# WeMos-WLED-V01-008.net
KiCad netlist of a schematic drawn in EAGLE
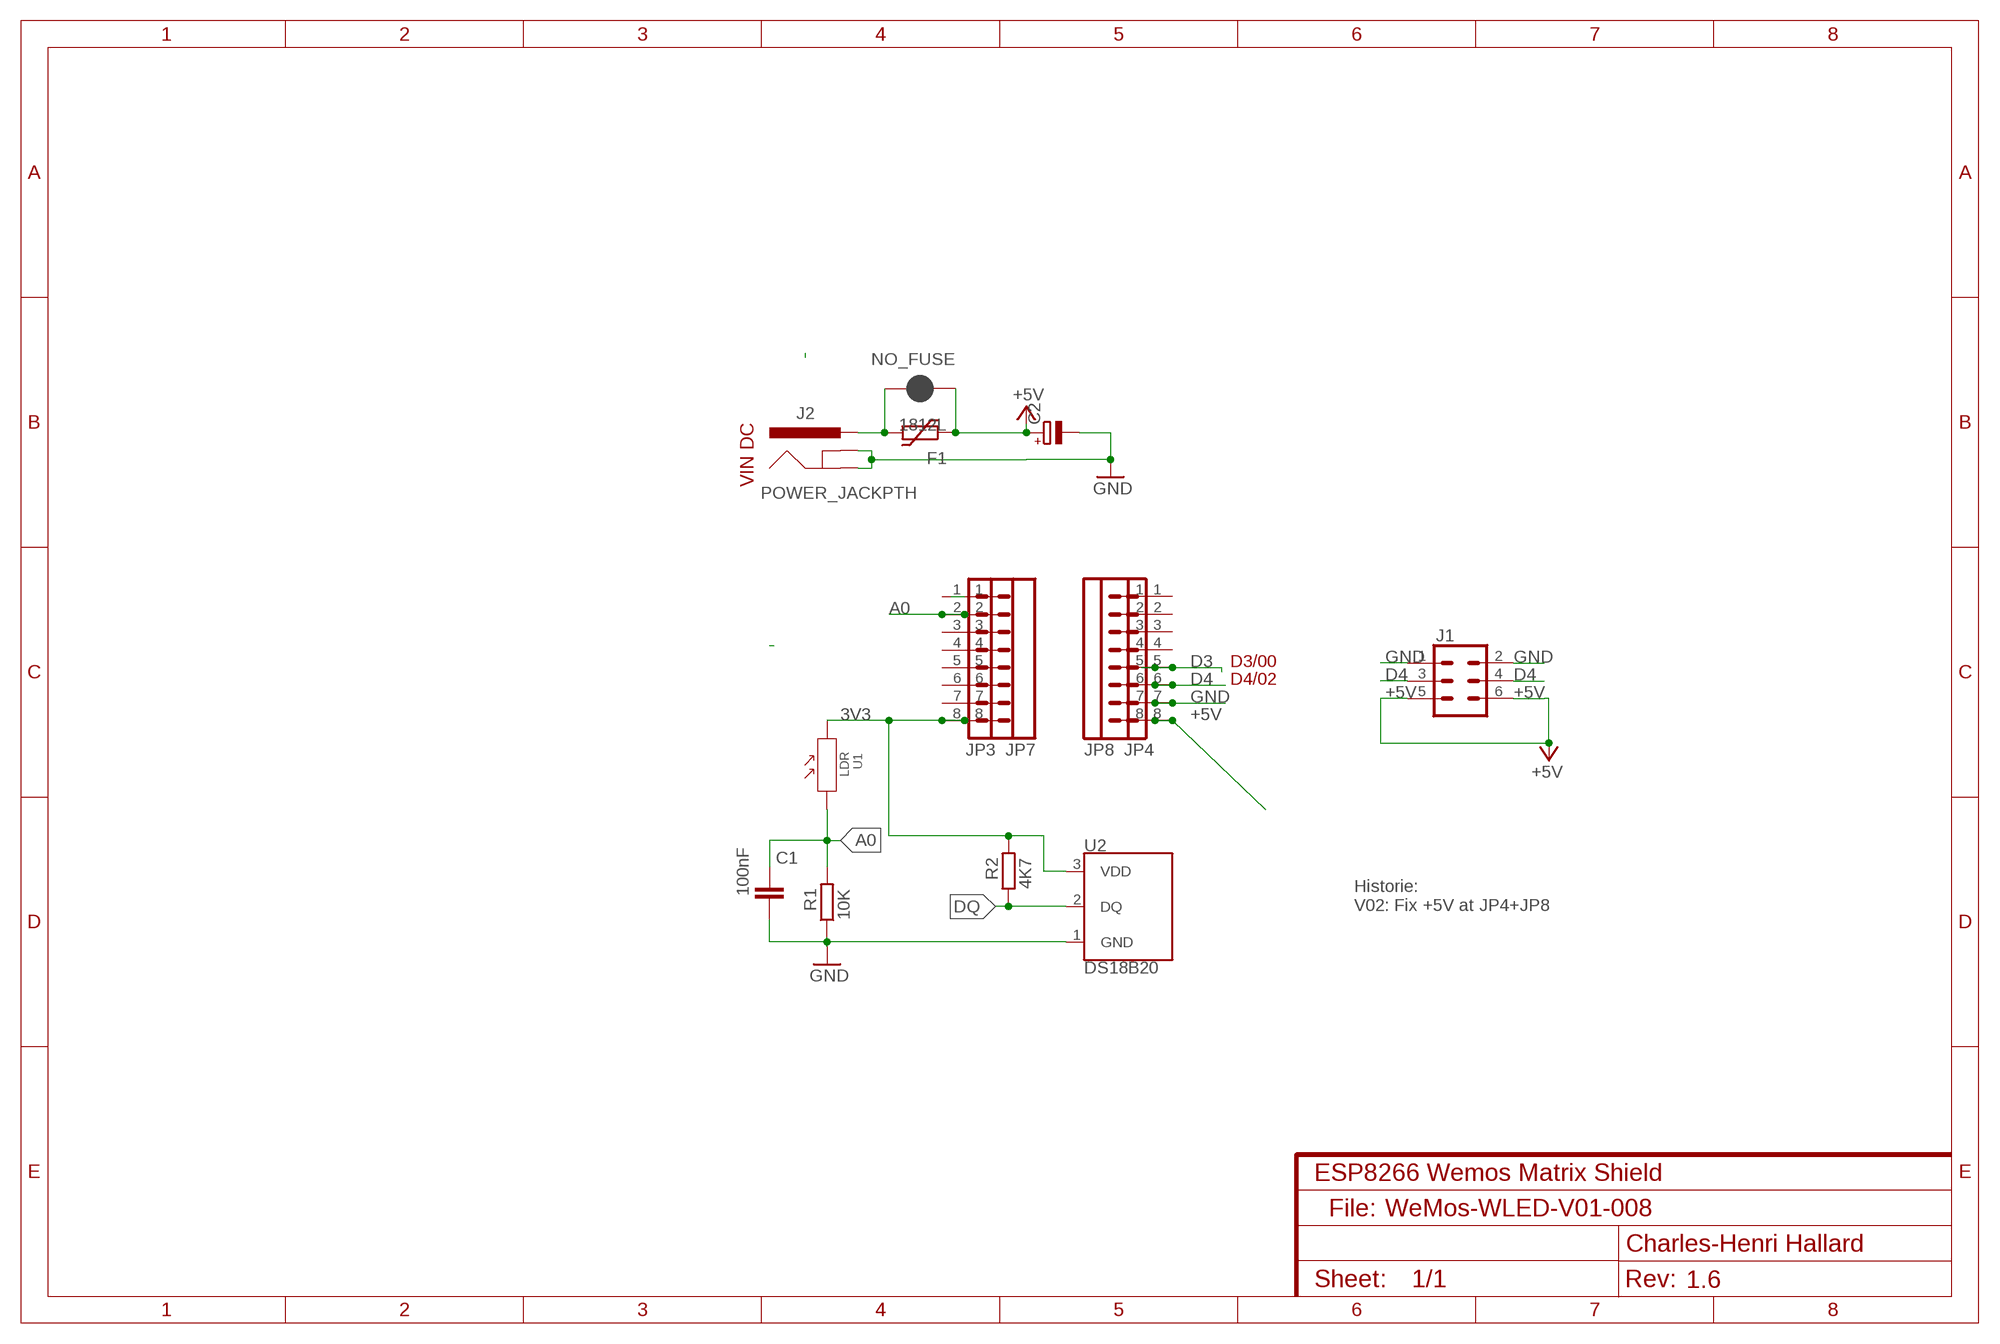
[diagram p0: schematic, sheet 1]

(export (version "E")
  (design (tool "Eeschema 10.0.6"))
  (components
    (comp (ref "C1")
      (value "100nF")
      (footprint "eagle-import:C0805")
      (libsource (lib "eagle-import") (part "C-EUC0805"))
    )
    (comp (ref "C2")
      (value "CPOL-EUE2.5-7")
      (footprint "eagle-import:E2,5-7")
      (libsource (lib "eagle-import") (part "CPOL-EUE2.5-7"))
    )
    (comp (ref "F1")
      (value "1812L")
      (footprint "eagle-import:1812L")
      (libsource (lib "eagle-import") (part "1812L"))
    )
    (comp (ref "J1")
      (value "CONN_03X22X3_SILK_MALE_PTH")
      (footprint "eagle-import:2X3")
      (libsource (lib "eagle-import") (part "CONN_03X22X3_SILK_MALE_PTH"))
    )
    (comp (ref "J2")
      (value "POWER_JACKPTH")
      (footprint "eagle-import:POWER_JACK_PTH")
      (libsource (lib "eagle-import") (part "POWER_JACKPTH"))
    )
    (comp (ref "JP3")
      (value "M08NO_SILK_FEMALE_PTH")
      (footprint "eagle-import:1X08_NO_SILK")
      (libsource (lib "eagle-import") (part "M08NO_SILK_FEMALE_PTH"))
    )
    (comp (ref "JP4")
      (value "M08NO_SILK_FEMALE_PTH")
      (footprint "eagle-import:1X08_NO_SILK")
      (libsource (lib "eagle-import") (part "M08NO_SILK_FEMALE_PTH"))
    )
    (comp (ref "JP7")
      (value "M08NO_SILK_FEMALE_PTH")
      (footprint "eagle-import:1X08_NO_SILK")
      (libsource (lib "eagle-import") (part "M08NO_SILK_FEMALE_PTH"))
    )
    (comp (ref "JP8")
      (value "M08NO_SILK_FEMALE_PTH")
      (footprint "eagle-import:1X08_NO_SILK")
      (libsource (lib "eagle-import") (part "M08NO_SILK_FEMALE_PTH"))
    )
    (comp (ref "NO_FUSE")
      (value "JUMPER-SMT_2_NC_PASTE_NO-SILK")
      (footprint "eagle-import:SMT-JUMPER_2_NC_PASTE_NO-SILK")
      (libsource (lib "eagle-import") (part "JUMPER-SMT_2_NC_PASTE_NO-SILK"))
    )
    (comp (ref "R1")
      (value "10K")
      (footprint "eagle-import:R0805")
      (libsource (lib "eagle-import") (part "R-EU_R0805"))
    )
    (comp (ref "R2")
      (value "4K7")
      (footprint "eagle-import:R0805")
      (libsource (lib "eagle-import") (part "R-EU_R0805"))
    )
    (comp (ref "U1")
      (value "LDR")
      (footprint "eagle-import:SNR2-3.0")
      (fields (field (name "MPN") "PHOTORESISTOR-5528-10K"))
      (libsource (lib "eagle-import") (part "PHOTORESISTOR-5528-10K(2P-5.0X4.2MM)"))
    )
    (comp (ref "U2")
      (value "DS18B20")
      (footprint "eagle-import:TO-92-AMMO")
      (libsource (lib "eagle-import") (part "DS18B20"))
    )
  )
  (nets
    (net (code "1") (name "+5V") (class "Default")
      (node (ref "C2") (pin "+") (pinfunction "+_+") (pintype "passive"))
      (node (ref "F1") (pin "P$1") (pinfunction "1_P$1") (pintype "passive"))
      (node (ref "J1") (pin "5") (pinfunction "5_5") (pintype "bidirectional"))
      (node (ref "J1") (pin "6") (pinfunction "6_6") (pintype "bidirectional"))
      (node (ref "JP4") (pin "8") (pinfunction "8_8") (pintype "passive"))
      (node (ref "JP8") (pin "8") (pinfunction "8_8") (pintype "passive"))
      (node (ref "NO_FUSE") (pin "1") (pinfunction "1_1") (pintype "passive"))
    )
    (net (code "2") (name "/3V3") (class "Default")
      (node (ref "JP3") (pin "8") (pinfunction "8_8") (pintype "passive"))
      (node (ref "JP7") (pin "8") (pinfunction "8_8") (pintype "passive"))
      (node (ref "R2") (pin "2") (pinfunction "2_2") (pintype "passive"))
      (node (ref "U1") (pin "2") (pinfunction "P$2_2") (pintype "bidirectional"))
      (node (ref "U2") (pin "3") (pinfunction "VDD_3") (pintype "power_in"))
    )
    (net (code "3") (name "/D3") (class "Default")
      (node (ref "JP4") (pin "5") (pinfunction "5_5") (pintype "passive"))
      (node (ref "JP8") (pin "5") (pinfunction "5_5") (pintype "passive"))
    )
    (net (code "4") (name "/D4") (class "Default")
      (node (ref "J1") (pin "3") (pinfunction "3_3") (pintype "bidirectional"))
      (node (ref "J1") (pin "4") (pinfunction "4_4") (pintype "bidirectional"))
      (node (ref "JP4") (pin "6") (pinfunction "6_6") (pintype "passive"))
      (node (ref "JP8") (pin "6") (pinfunction "6_6") (pintype "passive"))
    )
    (net (code "5") (name "A0") (class "Default")
      (node (ref "C1") (pin "1") (pinfunction "1_1") (pintype "passive"))
      (node (ref "JP3") (pin "2") (pinfunction "2_2") (pintype "passive"))
      (node (ref "JP7") (pin "2") (pinfunction "2_2") (pintype "passive"))
      (node (ref "R1") (pin "2") (pinfunction "2_2") (pintype "passive"))
      (node (ref "U1") (pin "1") (pinfunction "P$1_1") (pintype "bidirectional"))
    )
    (net (code "6") (name "DQ") (class "Default")
      (node (ref "R2") (pin "1") (pinfunction "1_1") (pintype "passive"))
      (node (ref "U2") (pin "2") (pinfunction "DQ_2") (pintype "bidirectional"))
    )
    (net (code "7") (name "GND") (class "Default")
      (node (ref "C1") (pin "2") (pinfunction "2_2") (pintype "passive"))
      (node (ref "C2") (pin "-") (pinfunction "-_-") (pintype "passive"))
      (node (ref "J1") (pin "1") (pinfunction "1_1") (pintype "bidirectional"))
      (node (ref "J1") (pin "2") (pinfunction "2_2") (pintype "bidirectional"))
      (node (ref "J2") (pin "GND") (pinfunction "GND_GND") (pintype "bidirectional"))
      (node (ref "J2") (pin "GNDBREAK") (pinfunction "GNDBREAK_GNDBREAK") (pintype "bidirectional"))
      (node (ref "JP4") (pin "7") (pinfunction "7_7") (pintype "passive"))
      (node (ref "JP8") (pin "7") (pinfunction "7_7") (pintype "passive"))
      (node (ref "R1") (pin "1") (pinfunction "1_1") (pintype "passive"))
      (node (ref "U2") (pin "1") (pinfunction "GND_1") (pintype "power_in"))
    )
    (net (code "8") (name "Net-(F1-2)") (class "Default")
      (node (ref "F1") (pin "P$2") (pinfunction "2_P$2") (pintype "passive"))
      (node (ref "J2") (pin "PWR") (pinfunction "PWR_PWR") (pintype "bidirectional"))
      (node (ref "NO_FUSE") (pin "2") (pinfunction "2_2") (pintype "passive"))
    )
    (net (code "9") (name "unconnected-(JP3-Pad1)") (class "Default")
      (node (ref "JP3") (pin "1") (pinfunction "1_1") (pintype "passive"))
    )
    (net (code "10") (name "unconnected-(JP3-Pad3)") (class "Default")
      (node (ref "JP3") (pin "3") (pinfunction "3_3") (pintype "passive"))
    )
    (net (code "11") (name "unconnected-(JP3-Pad4)") (class "Default")
      (node (ref "JP3") (pin "4") (pinfunction "4_4") (pintype "passive"))
    )
    (net (code "12") (name "unconnected-(JP3-Pad5)") (class "Default")
      (node (ref "JP3") (pin "5") (pinfunction "5_5") (pintype "passive"))
    )
    (net (code "13") (name "unconnected-(JP3-Pad6)") (class "Default")
      (node (ref "JP3") (pin "6") (pinfunction "6_6") (pintype "passive"))
    )
    (net (code "14") (name "unconnected-(JP3-Pad7)") (class "Default")
      (node (ref "JP3") (pin "7") (pinfunction "7_7") (pintype "passive"))
    )
    (net (code "15") (name "unconnected-(JP4-Pad1)") (class "Default")
      (node (ref "JP4") (pin "1") (pinfunction "1_1") (pintype "passive"))
    )
    (net (code "16") (name "unconnected-(JP4-Pad2)") (class "Default")
      (node (ref "JP4") (pin "2") (pinfunction "2_2") (pintype "passive"))
    )
    (net (code "17") (name "unconnected-(JP4-Pad3)") (class "Default")
      (node (ref "JP4") (pin "3") (pinfunction "3_3") (pintype "passive"))
    )
    (net (code "18") (name "unconnected-(JP4-Pad4)") (class "Default")
      (node (ref "JP4") (pin "4") (pinfunction "4_4") (pintype "passive"))
    )
    (net (code "19") (name "unconnected-(JP7-Pad1)") (class "Default")
      (node (ref "JP7") (pin "1") (pinfunction "1_1") (pintype "passive"))
    )
    (net (code "20") (name "unconnected-(JP7-Pad3)") (class "Default")
      (node (ref "JP7") (pin "3") (pinfunction "3_3") (pintype "passive"))
    )
    (net (code "21") (name "unconnected-(JP7-Pad4)") (class "Default")
      (node (ref "JP7") (pin "4") (pinfunction "4_4") (pintype "passive"))
    )
    (net (code "22") (name "unconnected-(JP7-Pad5)") (class "Default")
      (node (ref "JP7") (pin "5") (pinfunction "5_5") (pintype "passive"))
    )
    (net (code "23") (name "unconnected-(JP7-Pad6)") (class "Default")
      (node (ref "JP7") (pin "6") (pinfunction "6_6") (pintype "passive"))
    )
    (net (code "24") (name "unconnected-(JP7-Pad7)") (class "Default")
      (node (ref "JP7") (pin "7") (pinfunction "7_7") (pintype "passive"))
    )
    (net (code "25") (name "unconnected-(JP8-Pad1)") (class "Default")
      (node (ref "JP8") (pin "1") (pinfunction "1_1") (pintype "passive"))
    )
    (net (code "26") (name "unconnected-(JP8-Pad2)") (class "Default")
      (node (ref "JP8") (pin "2") (pinfunction "2_2") (pintype "passive"))
    )
    (net (code "27") (name "unconnected-(JP8-Pad3)") (class "Default")
      (node (ref "JP8") (pin "3") (pinfunction "3_3") (pintype "passive"))
    )
    (net (code "28") (name "unconnected-(JP8-Pad4)") (class "Default")
      (node (ref "JP8") (pin "4") (pinfunction "4_4") (pintype "passive"))
    )
  )
)
